# H1DR51.net
KiCad netlist of a schematic drawn in EAGLE
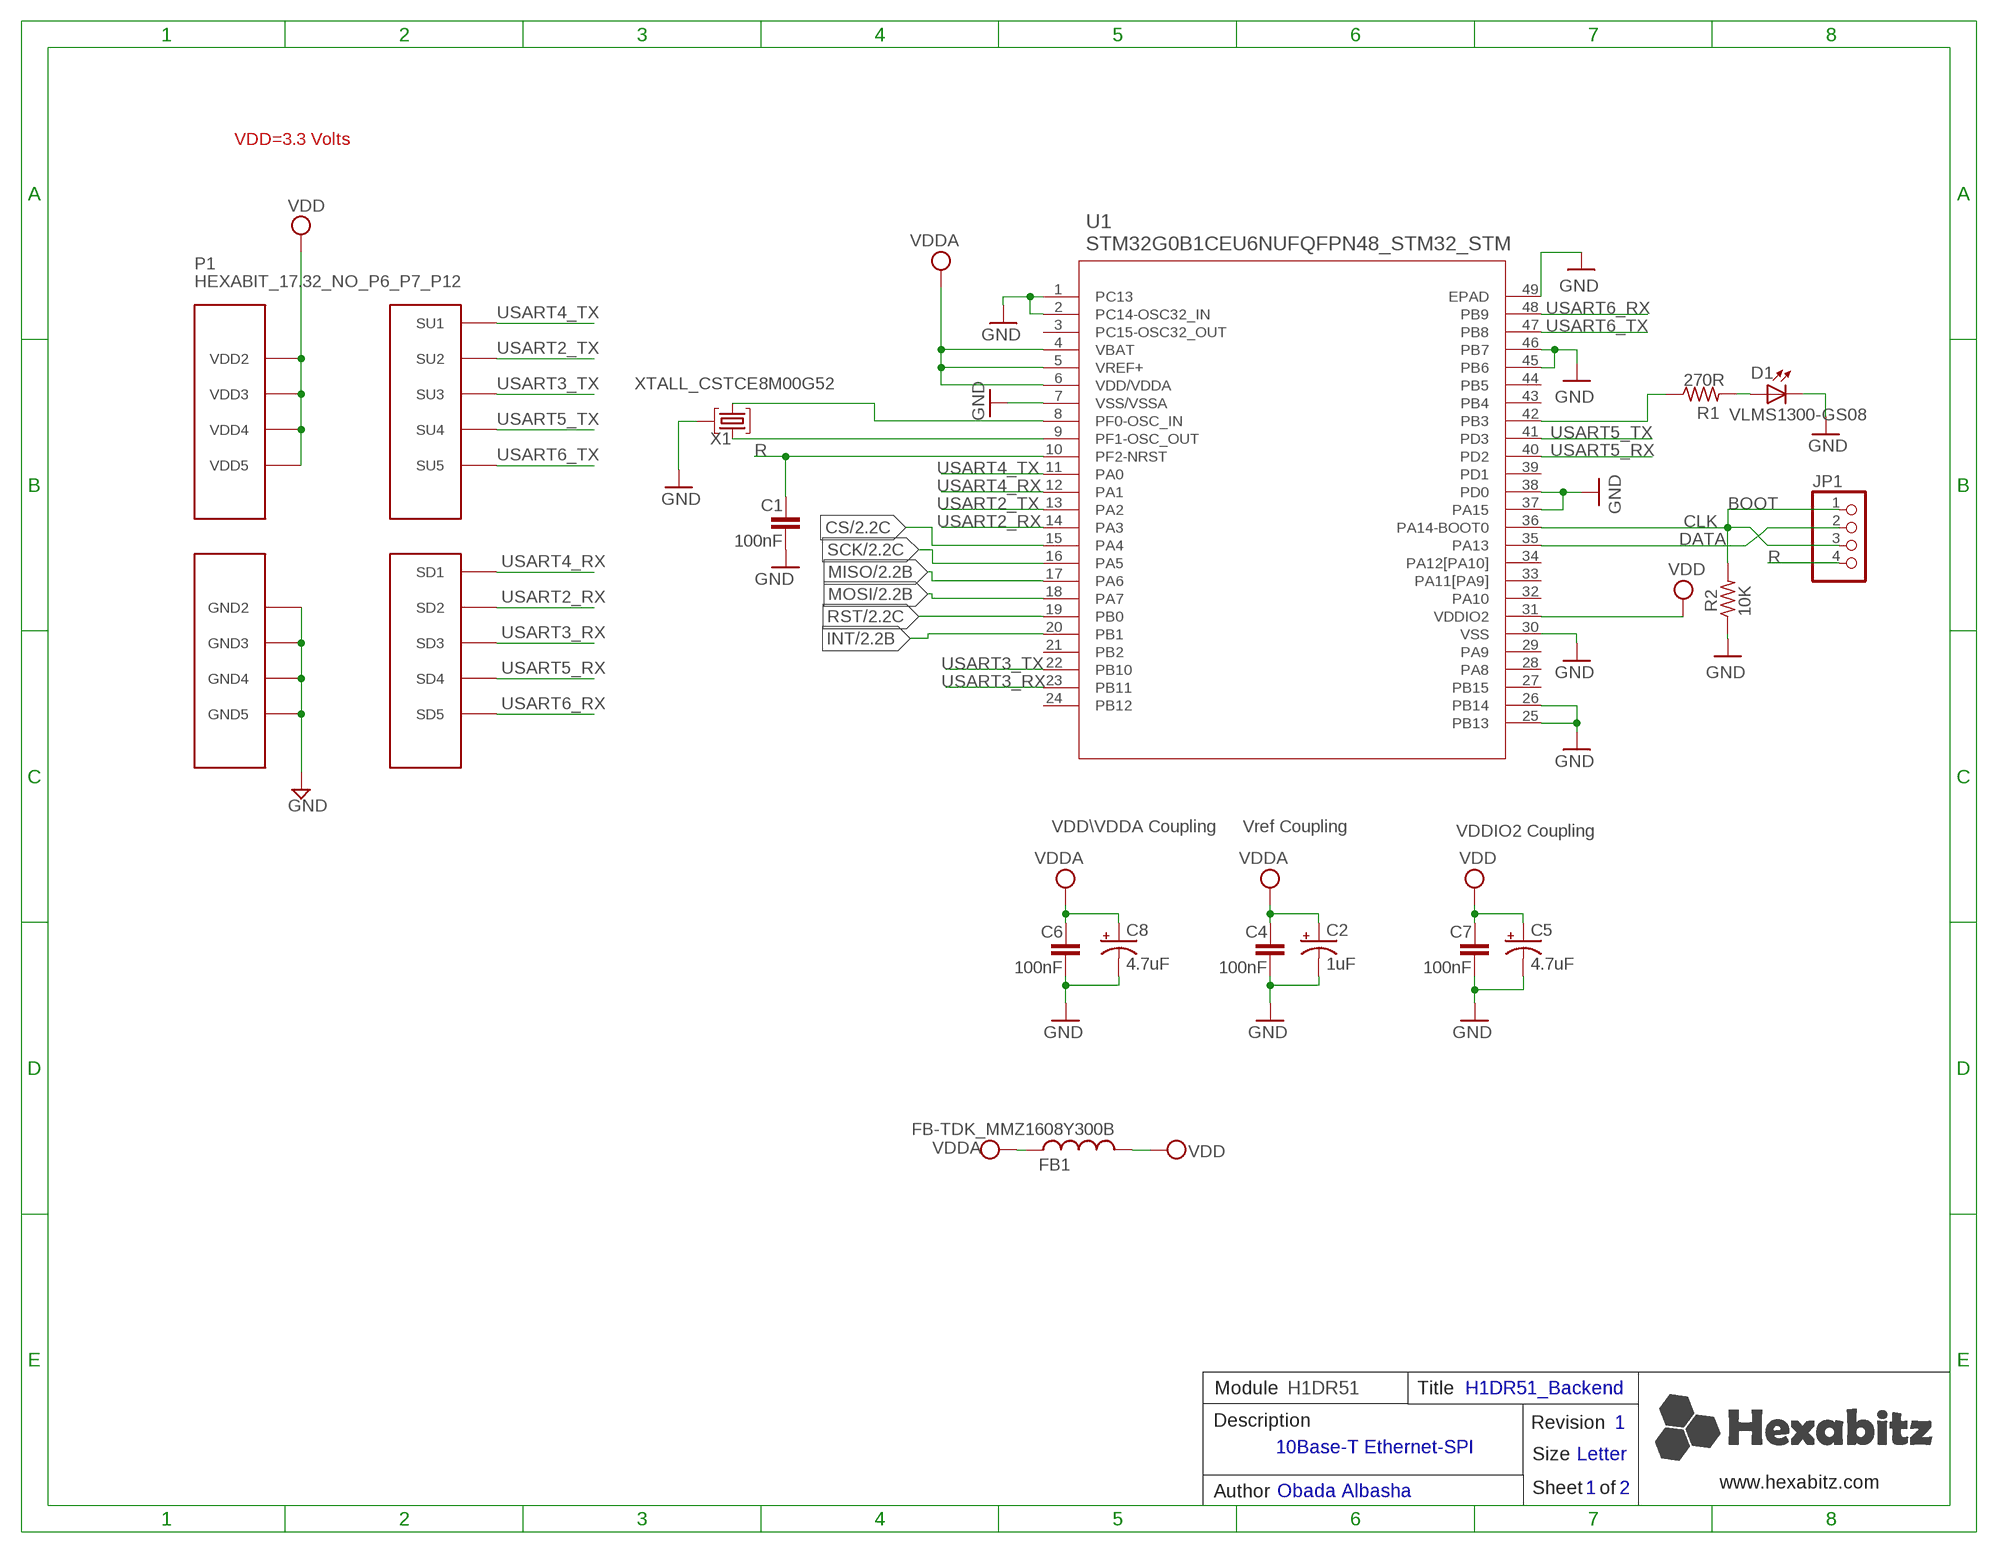
[diagram p0: schematic, sheet 1]
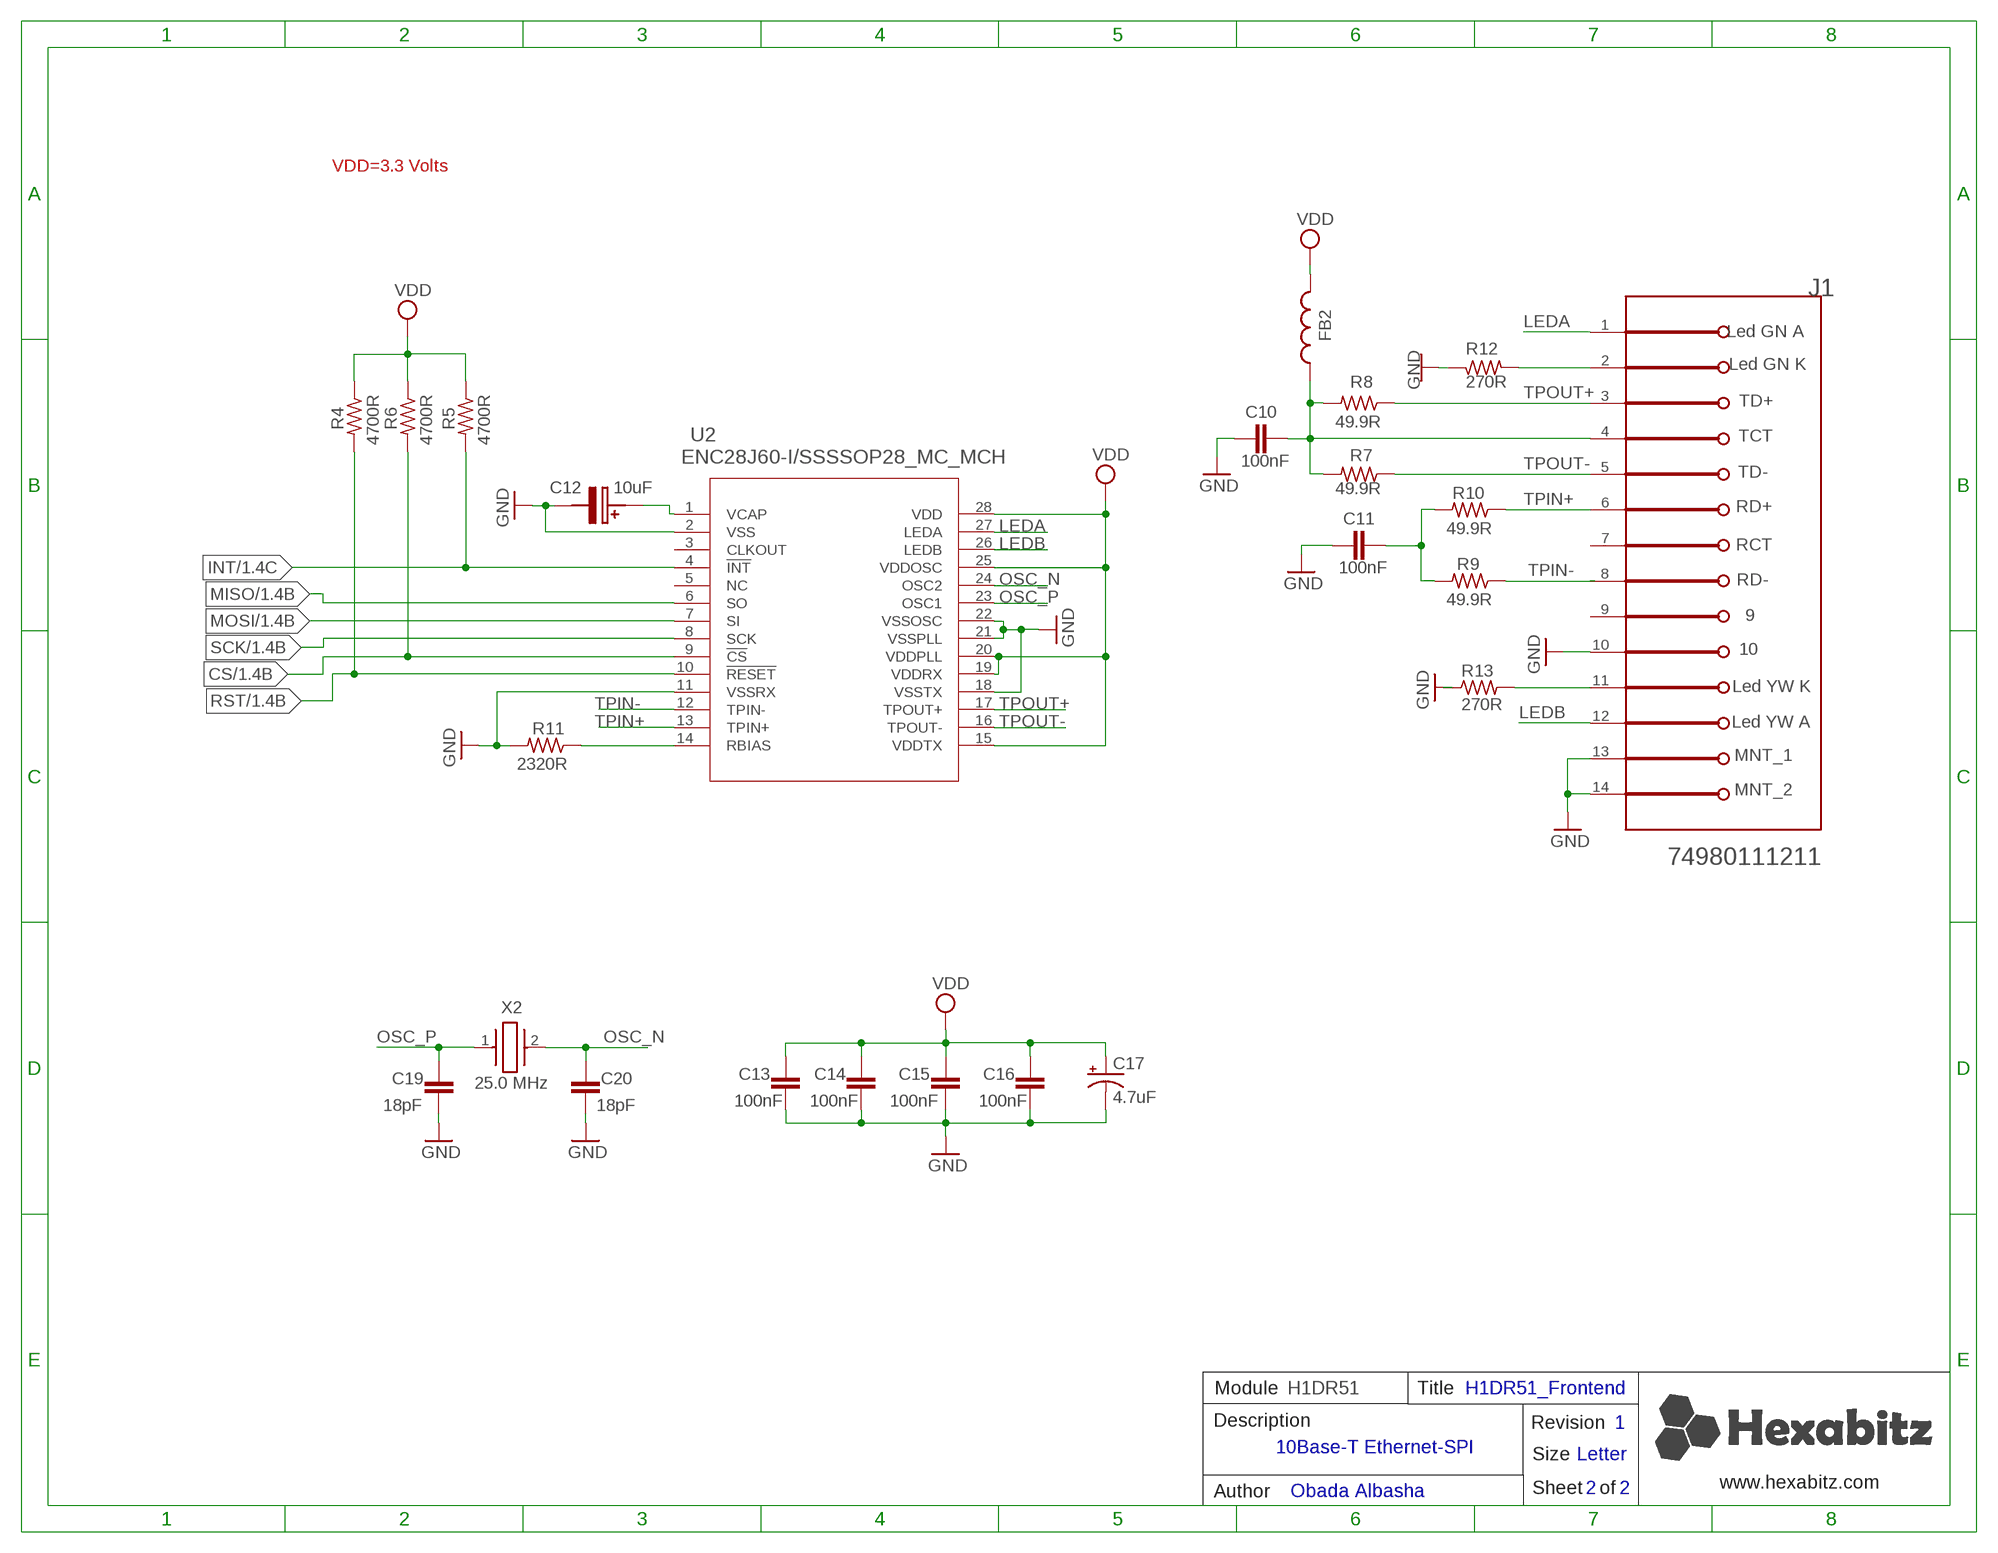
[diagram p1: schematic, sheet 2]

(export (version "E")
  (design (tool "Eeschema 10.0.6"))
  (components
    (comp (ref "C1")
      (value "100nF")
      (footprint "eagle-import:C-0603")
      (libsource (lib "eagle-import") (part "C-0603"))
    )
    (comp (ref "C2")
      (value "1uF")
      (footprint "eagle-import:C-0805-POL")
      (libsource (lib "eagle-import") (part "C-0805-POL"))
    )
    (comp (ref "C4")
      (value "100nF")
      (footprint "eagle-import:C-0603")
      (libsource (lib "eagle-import") (part "C-0603"))
    )
    (comp (ref "C5")
      (value "4.7uF")
      (footprint "eagle-import:C-0805-POL")
      (libsource (lib "eagle-import") (part "C-0805-POL"))
    )
    (comp (ref "C6")
      (value "100nF")
      (footprint "eagle-import:C-0603")
      (libsource (lib "eagle-import") (part "C-0603"))
    )
    (comp (ref "C7")
      (value "100nF")
      (footprint "eagle-import:C-0603")
      (libsource (lib "eagle-import") (part "C-0603"))
    )
    (comp (ref "C8")
      (value "4.7uF")
      (footprint "eagle-import:C-0805-POL")
      (libsource (lib "eagle-import") (part "C-0805-POL"))
    )
    (comp (ref "D1")
      (value "VLMS1300-GS08")
      (footprint "eagle-import:VLMS1300-GS08")
      (fields
        (field (name "MFN") "Vishay")
        (field (name "MPN") "VLMS1300-GS08")
        (field (name "OCTOPART_URL") "https://octopart.com/vlms1300-gs08-vishay-21709201?r=sp&s=_gcP4_q8T1SC6PJQPTQ9yA")
      )
      (libsource (lib "eagle-import") (part "VLMS1300-GS08"))
    )
    (comp (ref "FB1")
      (value "FB-TDK_MMZ1608Y300B")
      (footprint "eagle-import:FB-TDK_MMZ1608Y300B")
      (fields
        (field (name "MFN") "TDK ")
        (field (name "MPN") "MMZ1608Y300B")
        (field (name "OCTOPART_URL") "https://octopart.com/mmz1608y300b-tdk-368280?r=sp&s=cd9_2ZEqQ9q9UNBuQgHAiA")
      )
      (libsource (lib "eagle-import") (part "FB-TDK_MMZ1608Y300B"))
    )
    (comp (ref "JP1")
      (value "PINHD-1X4")
      (footprint "eagle-import:1X04")
      (libsource (lib "eagle-import") (part "PINHD-1X4"))
    )
    (comp (ref "P1")
      (value "HEXABIT_17.32_NO_P6_P7_P12")
      (footprint "eagle-import:HEXABIT_17.32_NO_P6_P7_P12")
      (libsource (lib "eagle-import") (part "HEXABIT_?_NO_P6_P7_P1217.32"))
    )
    (comp (ref "R1")
      (value "270R")
      (footprint "eagle-import:R-0603")
      (libsource (lib "eagle-import") (part "R-0603"))
    )
    (comp (ref "R2")
      (value "10K")
      (footprint "eagle-import:R-0603")
      (libsource (lib "eagle-import") (part "R-0603"))
    )
    (comp (ref "U1")
      (value "STM32G0B1CEU6NUFQFPN48_STM32_STM")
      (footprint "eagle-import:UFQFPN48_STM32_STM")
      (fields
        (field (name "MPN") "STM32G0B1CEU6N")
        (field (name "COPYRIGHT") "Copyright (C) 2022 Ultra Librarian. All rights reserved.")
      )
      (libsource (lib "eagle-import") (part "STM32G0B1CEU6NUFQFPN48_STM32_STM"))
    )
    (comp (ref "X1")
      (value "XTALL_CSTCE8M00G52")
      (footprint "eagle-import:XTALL_CSTCE8M00G52")
      (fields (field (name "MPN") "CSTCE8M00G52Z-R0"))
      (libsource (lib "eagle-import") (part "XTALL_CSTCE8M00G52"))
    )
    (comp (ref "C10")
      (value "100nF")
      (footprint "eagle-import:C-0603")
      (libsource (lib "eagle-import") (part "C-0603"))
    )
    (comp (ref "C11")
      (value "100nF")
      (footprint "eagle-import:C-0603")
      (libsource (lib "eagle-import") (part "C-0603"))
    )
    (comp (ref "C12")
      (value "10uF")
      (footprint "eagle-import:T491A")
      (fields
        (field (name "MANUFACTURER_PART_NUMBER") "T491A106K010AT")
        (field (name "MOUSER_PART_NUMBER") "80-T491A106K010")
      )
      (libsource (lib "eagle-import") (part "T491A106K010AT"))
    )
    (comp (ref "C13")
      (value "100nF")
      (footprint "eagle-import:C-0603")
      (libsource (lib "eagle-import") (part "C-0603"))
    )
    (comp (ref "C14")
      (value "100nF")
      (footprint "eagle-import:C-0603")
      (libsource (lib "eagle-import") (part "C-0603"))
    )
    (comp (ref "C15")
      (value "100nF")
      (footprint "eagle-import:C-0603")
      (libsource (lib "eagle-import") (part "C-0603"))
    )
    (comp (ref "C16")
      (value "100nF")
      (footprint "eagle-import:C-0603")
      (libsource (lib "eagle-import") (part "C-0603"))
    )
    (comp (ref "C17")
      (value "4.7uF")
      (footprint "eagle-import:C-0805-POL")
      (libsource (lib "eagle-import") (part "C-0805-POL"))
    )
    (comp (ref "C19")
      (value "18pF")
      (footprint "eagle-import:C-0603")
      (libsource (lib "eagle-import") (part "C-0603"))
    )
    (comp (ref "C20")
      (value "18pF")
      (footprint "eagle-import:C-0603")
      (libsource (lib "eagle-import") (part "C-0603"))
    )
    (comp (ref "FB2")
      (value "FB-TDK_MMZ1608Y300B")
      (footprint "eagle-import:FB-TDK_MMZ1608Y300B")
      (fields
        (field (name "MFN") "TDK ")
        (field (name "MPN") "MMZ1608Y300B")
        (field (name "OCTOPART_URL") "https://octopart.com/mmz1608y300b-tdk-368280?r=sp&s=cd9_2ZEqQ9q9UNBuQgHAiA")
      )
      (libsource (lib "eagle-import") (part "FB-TDK_MMZ1608Y300B"))
    )
    (comp (ref "J1")
      (value "WURTH_74980111211WURTH_74980111211_0_0")
      (footprint "eagle-import:WURTH_74980111211_0")
      (fields
        (field (name "DIGIKEY_PART_NUMBER") "732-4517-1-ND")
        (field (name "MF") "Wurth")
        (field (name "MOUSER_PART_NUMBER") "710-74980111211")
      )
      (libsource (lib "eagle-import") (part "WURTH_74980111211WURTH_74980111211_0_0"))
    )
    (comp (ref "R4")
      (value "4700R")
      (footprint "eagle-import:R-0603")
      (libsource (lib "eagle-import") (part "R-0603"))
    )
    (comp (ref "R5")
      (value "4700R")
      (footprint "eagle-import:R-0603")
      (libsource (lib "eagle-import") (part "R-0603"))
    )
    (comp (ref "R6")
      (value "4700R")
      (footprint "eagle-import:R-0603")
      (libsource (lib "eagle-import") (part "R-0603"))
    )
    (comp (ref "R7")
      (value "49.9R")
      (footprint "eagle-import:R-0603")
      (libsource (lib "eagle-import") (part "R-0603"))
    )
    (comp (ref "R8")
      (value "49.9R")
      (footprint "eagle-import:R-0603")
      (libsource (lib "eagle-import") (part "R-0603"))
    )
    (comp (ref "R9")
      (value "49.9R")
      (footprint "eagle-import:R-0603")
      (libsource (lib "eagle-import") (part "R-0603"))
    )
    (comp (ref "R10")
      (value "49.9R")
      (footprint "eagle-import:R-0603")
      (libsource (lib "eagle-import") (part "R-0603"))
    )
    (comp (ref "R11")
      (value "2320R")
      (footprint "eagle-import:R-0603")
      (libsource (lib "eagle-import") (part "R-0603"))
    )
    (comp (ref "R12")
      (value "270R")
      (footprint "eagle-import:R-0603")
      (libsource (lib "eagle-import") (part "R-0603"))
    )
    (comp (ref "R13")
      (value "270R")
      (footprint "eagle-import:R-0603")
      (libsource (lib "eagle-import") (part "R-0603"))
    )
    (comp (ref "U2")
      (value "ENC28J60-I/SSSSOP28_MC_MCH")
      (footprint "eagle-import:SSOP28_MC_MCH")
      (fields
        (field (name "MANUFACTURER_PART_NUMBER") "ENC28J60-I/SS")
        (field (name "COPYRIGHT") "Copyright (C) 2022 Ultra Librarian. All rights reserved.")
      )
      (libsource (lib "eagle-import") (part "ENC28J60-I/SSSSOP28_MC_MCH"))
    )
    (comp (ref "X2")
      (value "25.0 MHz")
      (footprint "eagle-import:ABM325000MHZB2T")
      (fields
        (field (name "MANUFACTURER_PART_NUMBER") "ABM3-25.000MHZ-B2-T")
        (field (name "MOUSER_PART_NUMBER") "815-ABM3-25-B2-T")
      )
      (libsource (lib "eagle-import") (part "ABM3-25.000MHZ-B2-T"))
    )
  )
  (nets
    (net (code "1") (name "CLK") (class "Default")
      (node (ref "JP1") (pin "1") (pinfunction "1_1") (pintype "passive"))
      (node (ref "JP1") (pin "3") (pinfunction "3_3") (pintype "passive"))
      (node (ref "R2") (pin "2") (pinfunction "2_2") (pintype "passive"))
      (node (ref "U1") (pin "36") (pinfunction "PA14-BOOT0_36") (pintype "bidirectional"))
    )
    (net (code "2") (name "CS") (class "Default")
      (node (ref "R6") (pin "2") (pinfunction "2_2") (pintype "passive"))
      (node (ref "U1") (pin "15") (pinfunction "PA4_15") (pintype "bidirectional"))
      (node (ref "U2") (pin "9") (pinfunction "~{CS}_9") (pintype "input"))
    )
    (net (code "3") (name "DATA") (class "Default")
      (node (ref "JP1") (pin "2") (pinfunction "2_2") (pintype "passive"))
      (node (ref "U1") (pin "35") (pinfunction "PA13_35") (pintype "bidirectional"))
    )
    (net (code "4") (name "GND") (class "Default")
      (node (ref "C1") (pin "2") (pinfunction "2_2") (pintype "passive"))
      (node (ref "C10") (pin "2") (pinfunction "2_2") (pintype "passive"))
      (node (ref "C11") (pin "2") (pinfunction "2_2") (pintype "passive"))
      (node (ref "C12") (pin "2") (pinfunction "-_2") (pintype "bidirectional"))
      (node (ref "C13") (pin "2") (pinfunction "2_2") (pintype "passive"))
      (node (ref "C14") (pin "2") (pinfunction "2_2") (pintype "passive"))
      (node (ref "C15") (pin "2") (pinfunction "2_2") (pintype "passive"))
      (node (ref "C16") (pin "2") (pinfunction "2_2") (pintype "passive"))
      (node (ref "C17") (pin "2") (pinfunction "-_2") (pintype "passive"))
      (node (ref "C19") (pin "2") (pinfunction "2_2") (pintype "passive"))
      (node (ref "C2") (pin "2") (pinfunction "-_2") (pintype "passive"))
      (node (ref "C20") (pin "2") (pinfunction "2_2") (pintype "passive"))
      (node (ref "C4") (pin "2") (pinfunction "2_2") (pintype "passive"))
      (node (ref "C5") (pin "2") (pinfunction "-_2") (pintype "passive"))
      (node (ref "C6") (pin "2") (pinfunction "2_2") (pintype "passive"))
      (node (ref "C7") (pin "2") (pinfunction "2_2") (pintype "passive"))
      (node (ref "C8") (pin "2") (pinfunction "-_2") (pintype "passive"))
      (node (ref "D1") (pin "C") (pinfunction "C_C") (pintype "passive"))
      (node (ref "J1") (pin "10") (pinfunction "10_10") (pintype "bidirectional"))
      (node (ref "J1") (pin "13") (pinfunction "MNT_1_13") (pintype "bidirectional"))
      (node (ref "J1") (pin "14") (pinfunction "MNT_2_14") (pintype "bidirectional"))
      (node (ref "P1") (pin "PAD_PD10") (pinfunction "GND4_PAD_PD10") (pintype "power_in"))
      (node (ref "P1") (pin "PAD_PD11") (pinfunction "GND5_PAD_PD11") (pintype "power_in"))
      (node (ref "P1") (pin "PAD_PD8") (pinfunction "GND2_PAD_PD8") (pintype "power_in"))
      (node (ref "P1") (pin "PAD_PD9") (pinfunction "GND3_PAD_PD9") (pintype "power_in"))
      (node (ref "R11") (pin "2") (pinfunction "2_2") (pintype "passive"))
      (node (ref "R12") (pin "1") (pinfunction "1_1") (pintype "passive"))
      (node (ref "R13") (pin "1") (pinfunction "1_1") (pintype "passive"))
      (node (ref "R2") (pin "1") (pinfunction "1_1") (pintype "passive"))
      (node (ref "U1") (pin "1") (pinfunction "PC13_1") (pintype "bidirectional"))
      (node (ref "U1") (pin "2") (pinfunction "PC14-OSC32_IN_2") (pintype "bidirectional"))
      (node (ref "U1") (pin "25") (pinfunction "PB13_25") (pintype "bidirectional"))
      (node (ref "U1") (pin "26") (pinfunction "PB14_26") (pintype "bidirectional"))
      (node (ref "U1") (pin "30") (pinfunction "VSS_30") (pintype "passive"))
      (node (ref "U1") (pin "37") (pinfunction "PA15_37") (pintype "bidirectional"))
      (node (ref "U1") (pin "38") (pinfunction "PD0_38") (pintype "bidirectional"))
      (node (ref "U1") (pin "45") (pinfunction "PB6_45") (pintype "bidirectional"))
      (node (ref "U1") (pin "46") (pinfunction "PB7_46") (pintype "bidirectional"))
      (node (ref "U1") (pin "49") (pinfunction "EPAD_49") (pintype "passive"))
      (node (ref "U1") (pin "7") (pinfunction "VSS/VSSA_7") (pintype "passive"))
      (node (ref "U2") (pin "11") (pinfunction "VSSRX_11") (pintype "power_in"))
      (node (ref "U2") (pin "18") (pinfunction "VSSTX_18") (pintype "power_in"))
      (node (ref "U2") (pin "2") (pinfunction "VSS_2") (pintype "power_in"))
      (node (ref "U2") (pin "21") (pinfunction "VSSPLL_21") (pintype "power_in"))
      (node (ref "U2") (pin "22") (pinfunction "VSSOSC_22") (pintype "power_in"))
      (node (ref "X1") (pin "P$2") (pinfunction "2_P$2") (pintype "passive"))
    )
    (net (code "5") (name "INT") (class "Default")
      (node (ref "R5") (pin "2") (pinfunction "2_2") (pintype "passive"))
      (node (ref "U1") (pin "20") (pinfunction "PB1_20") (pintype "bidirectional"))
      (node (ref "U2") (pin "4") (pinfunction "~{INT}_4") (pintype "output"))
    )
    (net (code "6") (name "LEDA") (class "Default")
      (node (ref "J1") (pin "1") (pinfunction "GREEN_ANODE_1") (pintype "bidirectional"))
      (node (ref "U2") (pin "27") (pinfunction "LEDA_27") (pintype "output"))
    )
    (net (code "7") (name "LEDB") (class "Default")
      (node (ref "J1") (pin "12") (pinfunction "YELLOW_ANODE_12") (pintype "bidirectional"))
      (node (ref "U2") (pin "26") (pinfunction "LEDB_26") (pintype "output"))
    )
    (net (code "8") (name "MISO") (class "Default")
      (node (ref "U1") (pin "17") (pinfunction "PA6_17") (pintype "bidirectional"))
      (node (ref "U2") (pin "6") (pinfunction "SO_6") (pintype "output"))
    )
    (net (code "9") (name "MOSI") (class "Default")
      (node (ref "U1") (pin "18") (pinfunction "PA7_18") (pintype "bidirectional"))
      (node (ref "U2") (pin "7") (pinfunction "SI_7") (pintype "input"))
    )
    (net (code "10") (name "Net-(C11-Pad1)") (class "Default")
      (node (ref "C11") (pin "1") (pinfunction "1_1") (pintype "passive"))
      (node (ref "R10") (pin "2") (pinfunction "2_2") (pintype "passive"))
      (node (ref "R9") (pin "2") (pinfunction "2_2") (pintype "passive"))
    )
    (net (code "11") (name "Net-(C12-+)") (class "Default")
      (node (ref "C12") (pin "1") (pinfunction "+_1") (pintype "bidirectional"))
      (node (ref "U2") (pin "1") (pinfunction "VCAP_1") (pintype "power_in"))
    )
    (net (code "12") (name "Net-(D1-PadA)") (class "Default")
      (node (ref "D1") (pin "A") (pinfunction "A_A") (pintype "passive"))
      (node (ref "R1") (pin "2") (pinfunction "2_2") (pintype "passive"))
    )
    (net (code "13") (name "Net-(J1-GREEN_CATHODE)") (class "Default")
      (node (ref "J1") (pin "2") (pinfunction "GREEN_CATHODE_2") (pintype "bidirectional"))
      (node (ref "R12") (pin "2") (pinfunction "2_2") (pintype "passive"))
    )
    (net (code "14") (name "Net-(J1-TCT)") (class "Default")
      (node (ref "C10") (pin "1") (pinfunction "1_1") (pintype "passive"))
      (node (ref "FB2") (pin "1") (pinfunction "1_1") (pintype "passive"))
      (node (ref "J1") (pin "4") (pinfunction "TCT_4") (pintype "bidirectional"))
      (node (ref "R7") (pin "2") (pinfunction "2_2") (pintype "passive"))
      (node (ref "R8") (pin "2") (pinfunction "2_2") (pintype "passive"))
    )
    (net (code "15") (name "Net-(J1-YELLOW_CATHODE)") (class "Default")
      (node (ref "J1") (pin "11") (pinfunction "YELLOW_CATHODE_11") (pintype "bidirectional"))
      (node (ref "R13") (pin "2") (pinfunction "2_2") (pintype "passive"))
    )
    (net (code "16") (name "Net-(U1-PB3)") (class "Default")
      (node (ref "R1") (pin "1") (pinfunction "1_1") (pintype "passive"))
      (node (ref "U1") (pin "42") (pinfunction "PB3_42") (pintype "bidirectional"))
    )
    (net (code "17") (name "Net-(U1-PF0-OSC_IN)") (class "Default")
      (node (ref "U1") (pin "8") (pinfunction "PF0-OSC_IN_8") (pintype "bidirectional"))
      (node (ref "X1") (pin "P$3") (pinfunction "3_P$3") (pintype "passive"))
    )
    (net (code "18") (name "Net-(U1-PF1-OSC_OUT)") (class "Default")
      (node (ref "U1") (pin "9") (pinfunction "PF1-OSC_OUT_9") (pintype "bidirectional"))
      (node (ref "X1") (pin "P$1") (pinfunction "1_P$1") (pintype "passive"))
    )
    (net (code "19") (name "Net-(U2-RBIAS)") (class "Default")
      (node (ref "R11") (pin "1") (pinfunction "1_1") (pintype "passive"))
      (node (ref "U2") (pin "14") (pinfunction "RBIAS_14") (pintype "input"))
    )
    (net (code "20") (name "OSC_N") (class "Default")
      (node (ref "C20") (pin "1") (pinfunction "1_1") (pintype "passive"))
      (node (ref "U2") (pin "24") (pinfunction "OSC2_24") (pintype "output"))
      (node (ref "X2") (pin "2") (pinfunction "2_2") (pintype "bidirectional"))
    )
    (net (code "21") (name "OSC_P") (class "Default")
      (node (ref "C19") (pin "1") (pinfunction "1_1") (pintype "passive"))
      (node (ref "U2") (pin "23") (pinfunction "OSC1_23") (pintype "input"))
      (node (ref "X2") (pin "1") (pinfunction "1_1") (pintype "bidirectional"))
    )
    (net (code "22") (name "R") (class "Default")
      (node (ref "C1") (pin "1") (pinfunction "1_1") (pintype "passive"))
      (node (ref "JP1") (pin "4") (pinfunction "4_4") (pintype "passive"))
      (node (ref "U1") (pin "10") (pinfunction "PF2-NRST_10") (pintype "bidirectional"))
    )
    (net (code "23") (name "RST") (class "Default")
      (node (ref "R4") (pin "2") (pinfunction "2_2") (pintype "passive"))
      (node (ref "U1") (pin "19") (pinfunction "PB0_19") (pintype "bidirectional"))
      (node (ref "U2") (pin "10") (pinfunction "~{RESET}_10") (pintype "input"))
    )
    (net (code "24") (name "SCK") (class "Default")
      (node (ref "U1") (pin "16") (pinfunction "PA5_16") (pintype "bidirectional"))
      (node (ref "U2") (pin "8") (pinfunction "SCK_8") (pintype "input"))
    )
    (net (code "25") (name "TPIN+") (class "Default")
      (node (ref "J1") (pin "6") (pinfunction "RD+_6") (pintype "bidirectional"))
      (node (ref "R10") (pin "1") (pinfunction "1_1") (pintype "passive"))
      (node (ref "U2") (pin "13") (pinfunction "TPIN+_13") (pintype "input"))
    )
    (net (code "26") (name "TPIN-") (class "Default")
      (node (ref "J1") (pin "8") (pinfunction "RD-_8") (pintype "bidirectional"))
      (node (ref "R9") (pin "1") (pinfunction "1_1") (pintype "passive"))
      (node (ref "U2") (pin "12") (pinfunction "TPIN-_12") (pintype "input"))
    )
    (net (code "27") (name "TPOUT+") (class "Default")
      (node (ref "J1") (pin "3") (pinfunction "TD+_3") (pintype "bidirectional"))
      (node (ref "R8") (pin "1") (pinfunction "1_1") (pintype "passive"))
      (node (ref "U2") (pin "17") (pinfunction "TPOUT+_17") (pintype "output"))
    )
    (net (code "28") (name "TPOUT-") (class "Default")
      (node (ref "J1") (pin "5") (pinfunction "TD-_5") (pintype "bidirectional"))
      (node (ref "R7") (pin "1") (pinfunction "1_1") (pintype "passive"))
      (node (ref "U2") (pin "16") (pinfunction "TPOUT-_16") (pintype "output"))
    )
    (net (code "29") (name "USART2_RX") (class "Default")
      (node (ref "P1") (pin "PAD_PD5") (pinfunction "SD2_PAD_PD5") (pintype "bidirectional"))
      (node (ref "U1") (pin "14") (pinfunction "PA3_14") (pintype "bidirectional"))
    )
    (net (code "30") (name "USART2_TX") (class "Default")
      (node (ref "P1") (pin "PAD_PU5") (pinfunction "SU2_PAD_PU5") (pintype "bidirectional"))
      (node (ref "U1") (pin "13") (pinfunction "PA2_13") (pintype "bidirectional"))
    )
    (net (code "31") (name "USART3_RX") (class "Default")
      (node (ref "P1") (pin "PAD_PD1") (pinfunction "SD3_PAD_PD1") (pintype "bidirectional"))
      (node (ref "U1") (pin "23") (pinfunction "PB11_23") (pintype "bidirectional"))
    )
    (net (code "32") (name "USART3_TX") (class "Default")
      (node (ref "P1") (pin "PAD_PU1") (pinfunction "SU3_PAD_PU1") (pintype "bidirectional"))
      (node (ref "U1") (pin "22") (pinfunction "PB10_22") (pintype "bidirectional"))
    )
    (net (code "33") (name "USART4_RX") (class "Default")
      (node (ref "P1") (pin "PAD_PD4") (pinfunction "SD1_PAD_PD4") (pintype "bidirectional"))
      (node (ref "U1") (pin "12") (pinfunction "PA1_12") (pintype "bidirectional"))
    )
    (net (code "34") (name "USART4_TX") (class "Default")
      (node (ref "P1") (pin "PAD_PU4") (pinfunction "SU1_PAD_PU4") (pintype "bidirectional"))
      (node (ref "U1") (pin "11") (pinfunction "PA0_11") (pintype "bidirectional"))
    )
    (net (code "35") (name "USART5_RX") (class "Default")
      (node (ref "P1") (pin "PAD_PD2") (pinfunction "SD4_PAD_PD2") (pintype "bidirectional"))
      (node (ref "U1") (pin "40") (pinfunction "PD2_40") (pintype "bidirectional"))
    )
    (net (code "36") (name "USART5_TX") (class "Default")
      (node (ref "P1") (pin "PAD_PU2") (pinfunction "SU4_PAD_PU2") (pintype "bidirectional"))
      (node (ref "U1") (pin "41") (pinfunction "PD3_41") (pintype "bidirectional"))
    )
    (net (code "37") (name "USART6_RX") (class "Default")
      (node (ref "P1") (pin "PAD_PD3") (pinfunction "SD5_PAD_PD3") (pintype "bidirectional"))
      (node (ref "U1") (pin "48") (pinfunction "PB9_48") (pintype "bidirectional"))
    )
    (net (code "38") (name "USART6_TX") (class "Default")
      (node (ref "P1") (pin "PAD_PU3") (pinfunction "SU5_PAD_PU3") (pintype "bidirectional"))
      (node (ref "U1") (pin "47") (pinfunction "PB8_47") (pintype "bidirectional"))
    )
    (net (code "39") (name "VDD") (class "Default")
      (node (ref "C13") (pin "1") (pinfunction "1_1") (pintype "passive"))
      (node (ref "C14") (pin "1") (pinfunction "1_1") (pintype "passive"))
      (node (ref "C15") (pin "1") (pinfunction "1_1") (pintype "passive"))
      (node (ref "C16") (pin "1") (pinfunction "1_1") (pintype "passive"))
      (node (ref "C17") (pin "1") (pinfunction "+_1") (pintype "passive"))
      (node (ref "C5") (pin "1") (pinfunction "+_1") (pintype "passive"))
      (node (ref "C7") (pin "1") (pinfunction "1_1") (pintype "passive"))
      (node (ref "FB1") (pin "2") (pinfunction "2_2") (pintype "passive"))
      (node (ref "FB2") (pin "2") (pinfunction "2_2") (pintype "passive"))
      (node (ref "P1") (pin "PAD_PU10") (pinfunction "VDD4_PAD_PU10") (pintype "power_in"))
      (node (ref "P1") (pin "PAD_PU11") (pinfunction "VDD5_PAD_PU11") (pintype "power_in"))
      (node (ref "P1") (pin "PAD_PU8") (pinfunction "VDD2_PAD_PU8") (pintype "power_in"))
      (node (ref "P1") (pin "PAD_PU9") (pinfunction "VDD3_PAD_PU9") (pintype "power_in"))
      (node (ref "R4") (pin "1") (pinfunction "1_1") (pintype "passive"))
      (node (ref "R5") (pin "1") (pinfunction "1_1") (pintype "passive"))
      (node (ref "R6") (pin "1") (pinfunction "1_1") (pintype "passive"))
      (node (ref "U1") (pin "31") (pinfunction "VDDIO2_31") (pintype "power_in"))
      (node (ref "U2") (pin "15") (pinfunction "VDDTX_15") (pintype "power_in"))
      (node (ref "U2") (pin "19") (pinfunction "VDDRX_19") (pintype "power_in"))
      (node (ref "U2") (pin "20") (pinfunction "VDDPLL_20") (pintype "power_in"))
      (node (ref "U2") (pin "25") (pinfunction "VDDOSC_25") (pintype "power_in"))
      (node (ref "U2") (pin "28") (pinfunction "VDD_28") (pintype "power_in"))
    )
    (net (code "40") (name "VDDA") (class "Default")
      (node (ref "C2") (pin "1") (pinfunction "+_1") (pintype "passive"))
      (node (ref "C4") (pin "1") (pinfunction "1_1") (pintype "passive"))
      (node (ref "C6") (pin "1") (pinfunction "1_1") (pintype "passive"))
      (node (ref "C8") (pin "1") (pinfunction "+_1") (pintype "passive"))
      (node (ref "FB1") (pin "1") (pinfunction "1_1") (pintype "passive"))
      (node (ref "U1") (pin "4") (pinfunction "VBAT_4") (pintype "power_in"))
      (node (ref "U1") (pin "5") (pinfunction "VREF+_5") (pintype "power_in"))
      (node (ref "U1") (pin "6") (pinfunction "VDD/VDDA_6") (pintype "power_in"))
    )
    (net (code "41") (name "unconnected-(J1-Pad9)") (class "Default")
      (node (ref "J1") (pin "9") (pinfunction "9_9") (pintype "bidirectional"))
    )
    (net (code "42") (name "unconnected-(J1-RCT-Pad7)") (class "Default")
      (node (ref "J1") (pin "7") (pinfunction "RCT_7") (pintype "bidirectional"))
    )
    (net (code "43") (name "unconnected-(U1-PA8-Pad28)") (class "Default")
      (node (ref "U1") (pin "28") (pinfunction "PA8_28") (pintype "bidirectional"))
    )
    (net (code "44") (name "unconnected-(U1-PA9-Pad29)") (class "Default")
      (node (ref "U1") (pin "29") (pinfunction "PA9_29") (pintype "bidirectional"))
    )
    (net (code "45") (name "unconnected-(U1-PA10-Pad32)") (class "Default")
      (node (ref "U1") (pin "32") (pinfunction "PA10_32") (pintype "bidirectional"))
    )
    (net (code "46") (name "unconnected-(U1-PA11[PA9]-Pad33)") (class "Default")
      (node (ref "U1") (pin "33") (pinfunction "PA11[PA9]_33") (pintype "bidirectional"))
    )
    (net (code "47") (name "unconnected-(U1-PA12[PA10]-Pad34)") (class "Default")
      (node (ref "U1") (pin "34") (pinfunction "PA12[PA10]_34") (pintype "bidirectional"))
    )
    (net (code "48") (name "unconnected-(U1-PB2-Pad21)") (class "Default")
      (node (ref "U1") (pin "21") (pinfunction "PB2_21") (pintype "bidirectional"))
    )
    (net (code "49") (name "unconnected-(U1-PB4-Pad43)") (class "Default")
      (node (ref "U1") (pin "43") (pinfunction "PB4_43") (pintype "bidirectional"))
    )
    (net (code "50") (name "unconnected-(U1-PB5-Pad44)") (class "Default")
      (node (ref "U1") (pin "44") (pinfunction "PB5_44") (pintype "bidirectional"))
    )
    (net (code "51") (name "unconnected-(U1-PB12-Pad24)") (class "Default")
      (node (ref "U1") (pin "24") (pinfunction "PB12_24") (pintype "bidirectional"))
    )
    (net (code "52") (name "unconnected-(U1-PB15-Pad27)") (class "Default")
      (node (ref "U1") (pin "27") (pinfunction "PB15_27") (pintype "bidirectional"))
    )
    (net (code "53") (name "unconnected-(U1-PC15-OSC32_OUT-Pad3)") (class "Default")
      (node (ref "U1") (pin "3") (pinfunction "PC15-OSC32_OUT_3") (pintype "bidirectional"))
    )
    (net (code "54") (name "unconnected-(U1-PD1-Pad39)") (class "Default")
      (node (ref "U1") (pin "39") (pinfunction "PD1_39") (pintype "bidirectional"))
    )
    (net (code "55") (name "unconnected-(U2-CLKOUT-Pad3)") (class "Default")
      (node (ref "U2") (pin "3") (pinfunction "CLKOUT_3") (pintype "output"))
    )
    (net (code "56") (name "unconnected-(U2-NC-Pad5)") (class "Default")
      (node (ref "U2") (pin "5") (pinfunction "NC_5") (pintype "no_connect"))
    )
  )
)
